# Electrode-Front-End-Analog.net
KiCad netlist of a schematic drawn in Altium Designer
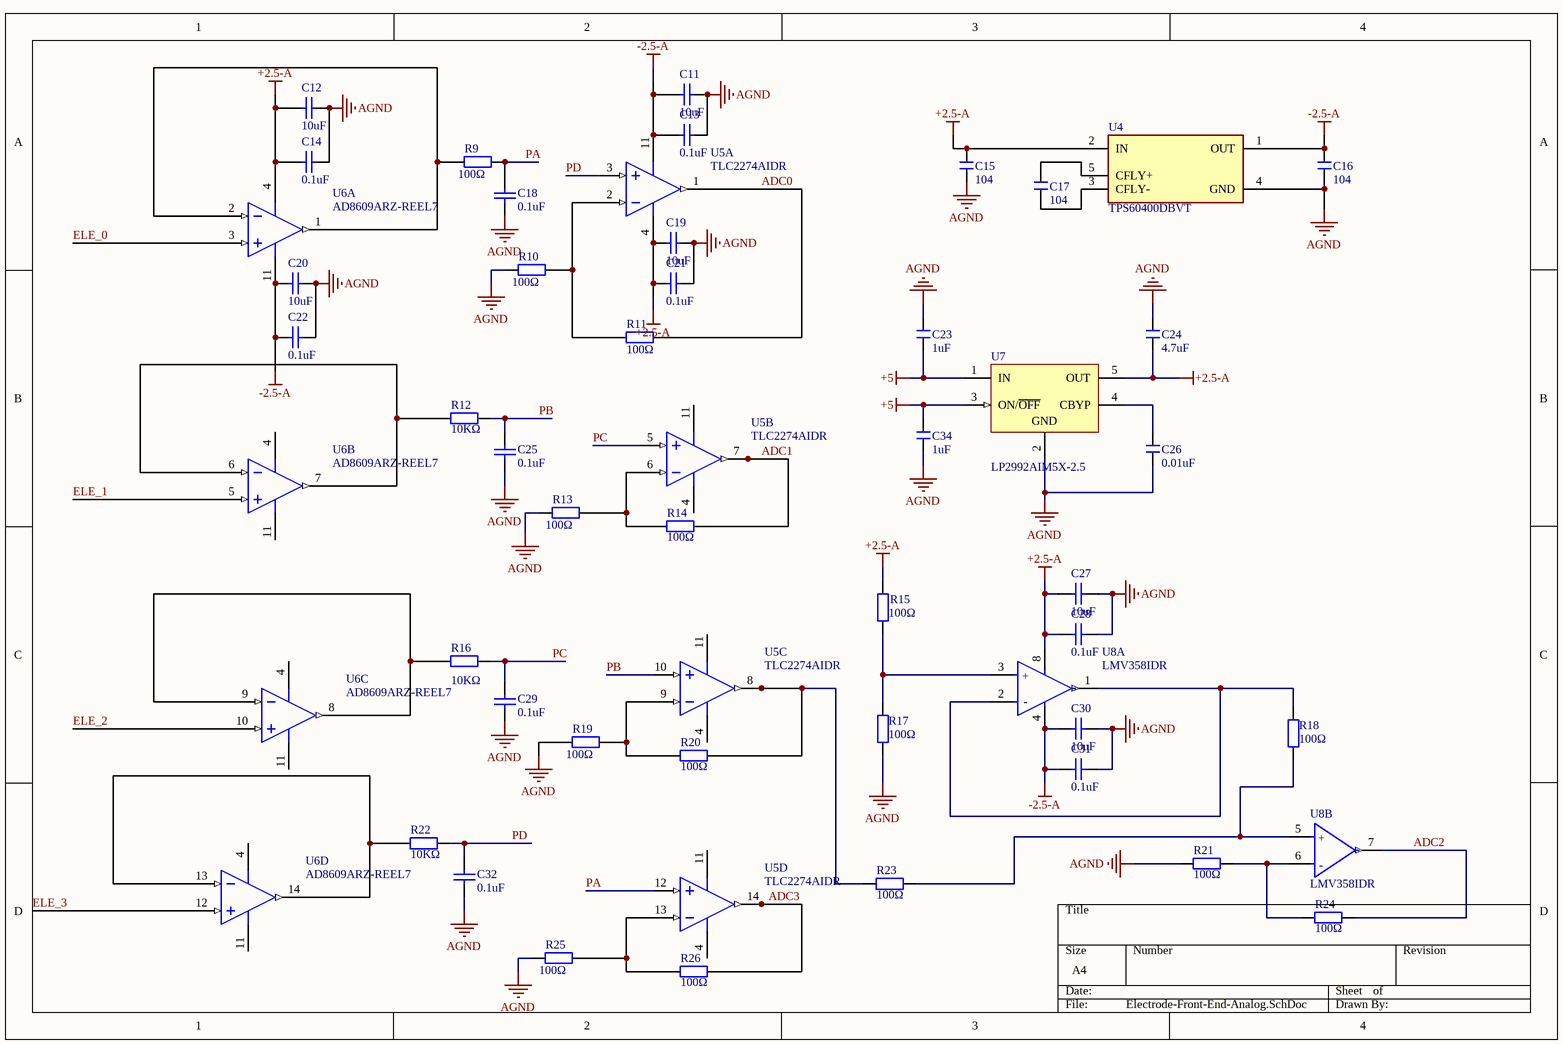
[diagram p0: Electrode-Front-End-Analog.SchDoc]

(export (version "E")
  (design (tool "Eeschema 10.0.6"))
  (components
    (comp (ref "C11")
      (value "10uF")
      (footprint "C 0603_L")
      (description "贴片电容")
      (libsource (lib "Miscellaneous Devices LC") (part "0603 10uF (106) 10% 10V"))
    )
    (comp (ref "C12")
      (value "10uF")
      (footprint "C 0603_L")
      (description "贴片电容")
      (libsource (lib "Miscellaneous Devices LC") (part "0603 10uF (106) 10% 10V"))
    )
    (comp (ref "C13")
      (value "0.1uF")
      (footprint "C 0603_L")
      (description "贴片电容")
      (libsource (lib "Miscellaneous Devices LC") (part "0603 100nF (104) 10% 50V"))
    )
    (comp (ref "C14")
      (value "0.1uF")
      (footprint "C 0603_L")
      (description "贴片电容")
      (libsource (lib "Miscellaneous Devices LC") (part "0603 100nF (104) 10% 50V"))
    )
    (comp (ref "C15")
      (value "104")
      (footprint "C 0603_L")
      (description "无极性贴片电容")
      (libsource (lib "电容-电阻-电感-电位器") (part "C"))
    )
    (comp (ref "C16")
      (value "104")
      (footprint "C 0603_L")
      (description "无极性贴片电容")
      (libsource (lib "电容-电阻-电感-电位器") (part "C"))
    )
    (comp (ref "C17")
      (value "104")
      (footprint "C 0603_L")
      (description "无极性贴片电容")
      (libsource (lib "电容-电阻-电感-电位器") (part "C"))
    )
    (comp (ref "C18")
      (value "0.1uF")
      (footprint "C 0603_L")
      (description "贴片电容")
      (libsource (lib "Miscellaneous Devices LC") (part "0603 100nF (104) 10% 50V"))
    )
    (comp (ref "C19")
      (value "10uF")
      (footprint "C 0603_L")
      (description "贴片电容")
      (libsource (lib "Miscellaneous Devices LC") (part "0603 10uF (106) 10% 10V"))
    )
    (comp (ref "C20")
      (value "10uF")
      (footprint "C 0603_L")
      (description "贴片电容")
      (libsource (lib "Miscellaneous Devices LC") (part "0603 10uF (106) 10% 10V"))
    )
    (comp (ref "C21")
      (value "0.1uF")
      (footprint "C 0603_L")
      (description "贴片电容")
      (libsource (lib "Miscellaneous Devices LC") (part "0603 100nF (104) 10% 50V"))
    )
    (comp (ref "C22")
      (value "0.1uF")
      (footprint "C 0603_L")
      (description "贴片电容")
      (libsource (lib "Miscellaneous Devices LC") (part "0603 100nF (104) 10% 50V"))
    )
    (comp (ref "C23")
      (value "1uF")
      (footprint "C 0603_L")
      (description "无极性贴片电容")
      (libsource (lib "电容-电阻-电感-电位器") (part "C"))
    )
    (comp (ref "C24")
      (value "4.7uF")
      (footprint "C 0603_L")
      (description "无极性贴片电容")
      (libsource (lib "电容-电阻-电感-电位器") (part "C"))
    )
    (comp (ref "C25")
      (value "0.1uF")
      (footprint "C 0603_L")
      (description "贴片电容")
      (libsource (lib "Miscellaneous Devices LC") (part "0603 100nF (104) 10% 50V"))
    )
    (comp (ref "C26")
      (value "0.01uF")
      (footprint "C 0603_L")
      (description "无极性贴片电容")
      (libsource (lib "电容-电阻-电感-电位器") (part "C"))
    )
    (comp (ref "C27")
      (value "10uF")
      (footprint "C 0603_L")
      (description "贴片电容")
      (libsource (lib "Miscellaneous Devices LC") (part "0603 10uF (106) 10% 10V"))
    )
    (comp (ref "C28")
      (value "0.1uF")
      (footprint "C 0603_L")
      (description "贴片电容")
      (libsource (lib "Miscellaneous Devices LC") (part "0603 100nF (104) 10% 50V"))
    )
    (comp (ref "C29")
      (value "0.1uF")
      (footprint "C 0603_L")
      (description "贴片电容")
      (libsource (lib "Miscellaneous Devices LC") (part "0603 100nF (104) 10% 50V"))
    )
    (comp (ref "C30")
      (value "10uF")
      (footprint "C 0603_L")
      (description "贴片电容")
      (libsource (lib "Miscellaneous Devices LC") (part "0603 10uF (106) 10% 10V"))
    )
    (comp (ref "C31")
      (value "0.1uF")
      (footprint "C 0603_L")
      (description "贴片电容")
      (libsource (lib "Miscellaneous Devices LC") (part "0603 100nF (104) 10% 50V"))
    )
    (comp (ref "C32")
      (value "0.1uF")
      (footprint "C 0603_L")
      (description "贴片电容")
      (libsource (lib "Miscellaneous Devices LC") (part "0603 100nF (104) 10% 50V"))
    )
    (comp (ref "C34")
      (value "1uF")
      (footprint "C 0603_L")
      (description "无极性贴片电容")
      (libsource (lib "电容-电阻-电感-电位器") (part "C"))
    )
    (comp (ref "R9")
      (value "100Ω")
      (footprint "R 0603_L")
      (description "贴片电阻")
      (libsource (lib "") (part "0603 100Ω (1000) 1%_1"))
    )
    (comp (ref "R10")
      (value "100Ω")
      (footprint "R 0603_L")
      (description "贴片电阻")
      (libsource (lib "") (part "0603 100Ω (1000) 1%_1"))
    )
    (comp (ref "R11")
      (value "100Ω")
      (footprint "R 0603_L")
      (description "贴片电阻")
      (libsource (lib "") (part "0603 100Ω (1000) 1%_1"))
    )
    (comp (ref "R12")
      (value "10KΩ")
      (footprint "R 0603_L")
      (description "贴片电阻")
      (libsource (lib "") (part "0603 100Ω (1000) 1%_1"))
    )
    (comp (ref "R13")
      (value "100Ω")
      (footprint "R 0603_L")
      (description "贴片电阻")
      (libsource (lib "") (part "0603 100Ω (1000) 1%_1"))
    )
    (comp (ref "R14")
      (value "100Ω")
      (footprint "R 0603_L")
      (description "贴片电阻")
      (libsource (lib "") (part "0603 100Ω (1000) 1%_1"))
    )
    (comp (ref "R15")
      (value "100Ω")
      (footprint "R 0603_L")
      (description "贴片电阻")
      (libsource (lib "") (part "0603 100Ω (1000) 1%_2"))
    )
    (comp (ref "R16")
      (value "10KΩ")
      (footprint "R 0603_L")
      (description "贴片电阻")
      (libsource (lib "") (part "0603 100Ω (1000) 1%_1"))
    )
    (comp (ref "R17")
      (value "100Ω")
      (footprint "R 0603_L")
      (description "贴片电阻")
      (libsource (lib "") (part "0603 100Ω (1000) 1%_2"))
    )
    (comp (ref "R18")
      (value "100Ω")
      (footprint "R 0603_L")
      (description "贴片电阻")
      (libsource (lib "") (part "0603 100Ω (1000) 1%_2"))
    )
    (comp (ref "R19")
      (value "100Ω")
      (footprint "R 0603_L")
      (description "贴片电阻")
      (libsource (lib "") (part "0603 100Ω (1000) 1%_1"))
    )
    (comp (ref "R20")
      (value "100Ω")
      (footprint "R 0603_L")
      (description "贴片电阻")
      (libsource (lib "") (part "0603 100Ω (1000) 1%_1"))
    )
    (comp (ref "R21")
      (value "100Ω")
      (footprint "R 0603_L")
      (description "贴片电阻")
      (libsource (lib "Miscellaneous Devices LC") (part "0603 100Ω (1000) 1%"))
    )
    (comp (ref "R22")
      (value "10KΩ")
      (footprint "R 0603_L")
      (description "贴片电阻")
      (libsource (lib "") (part "0603 100Ω (1000) 1%_1"))
    )
    (comp (ref "R23")
      (value "100Ω")
      (footprint "R 0603_L")
      (description "贴片电阻")
      (libsource (lib "Miscellaneous Devices LC") (part "0603 100Ω (1000) 1%"))
    )
    (comp (ref "R24")
      (value "100Ω")
      (footprint "R 0603_L")
      (description "贴片电阻")
      (libsource (lib "Miscellaneous Devices LC") (part "0603 100Ω (1000) 1%"))
    )
    (comp (ref "R25")
      (value "100Ω")
      (footprint "R 0603_L")
      (description "贴片电阻")
      (libsource (lib "") (part "0603 100Ω (1000) 1%_1"))
    )
    (comp (ref "R26")
      (value "100Ω")
      (footprint "R 0603_L")
      (description "贴片电阻")
      (libsource (lib "") (part "0603 100Ω (1000) 1%_1"))
    )
    (comp (ref "U4")
      (value "TPS60400DBVT")
      (footprint "FP-DBV0005A-IPC_C")
      (description "IC REG CHARG PUMP INV 60MA SOT23")
      (libsource (lib "Altium Content Vault") (part "419acff30fa379e0ae0717d32e86a44"))
    )
    (comp (ref "U5")
      (value "TLC2274AIDR")
      (footprint "D0014A_L")
      (fields (field (name "MANUFACTURER") "Texas Instruments"))
      (libsource (lib "Altium Content Vault") (part "TI-TLC2274X-14"))
    )
    (comp (ref "U6")
      (value "AD8609ARZ-REEL7")
      (footprint "ADI-R-14_N")
      (fields (field (name "MANUFACTURER") "Analog Devices") (field (name "GENERIC PART NUMBER") "AD8609"))
      (libsource (lib "Altium Content Vault") (part "ADI-ADxxxx_OPxxxx-X-14"))
    )
    (comp (ref "U7")
      (value "LP2992AIM5X-2.5")
      (footprint "MF05A_M")
      (description "Micropower 250 mA Low-Noise Ultra Low-Dropout Regulator, 5-pin SOT-23")
      (fields (field (name "MANUFACTURER") "National Semiconductor"))
      (libsource (lib "Altium Content Vault") (part "PM-REG-LP2985-SOT5"))
    )
    (comp (ref "U8")
      (value "LMV358IDR")
      (footprint "FP-D0008A-MFG")
      (description "IC OPAMP GP 2 CIRCUIT 8SOIC")
      (libsource (lib "Altium Content Vault") (part "1f85fec4e6914445158f776dbf16c1d"))
    )
  )
  (nets
    (net (code "1") (name "+2.5-A") (class "Default")
      (node (ref "C12") (pin "1") (pinfunction "1_1") (pintype "passive"))
      (node (ref "C14") (pin "1") (pinfunction "1_1") (pintype "passive"))
      (node (ref "C15") (pin "2") (pinfunction "2_2") (pintype "passive"))
      (node (ref "C19") (pin "1") (pinfunction "1_1") (pintype "passive"))
      (node (ref "C21") (pin "1") (pinfunction "1_1") (pintype "passive"))
      (node (ref "C24") (pin "1") (pinfunction "1_1") (pintype "passive"))
      (node (ref "C27") (pin "1") (pinfunction "1_1") (pintype "passive"))
      (node (ref "C28") (pin "1") (pinfunction "1_1") (pintype "passive"))
      (node (ref "R15") (pin "2") (pinfunction "2_2") (pintype "passive"))
      (node (ref "U4") (pin "2") (pinfunction "IN_2") (pintype "power_in"))
      (node (ref "U5") (pin "4") (pinfunction "VDD+_4") (pintype "power_in"))
      (node (ref "U6") (pin "4") (pinfunction "+V_4") (pintype "power_in"))
      (node (ref "U7") (pin "5") (pinfunction "OUT_5") (pintype "power_in"))
      (node (ref "U8") (pin "8") (pinfunction "VCC+_8") (pintype "power_in"))
    )
    (net (code "2") (name "+5") (class "Default")
      (node (ref "C23") (pin "1") (pinfunction "1_1") (pintype "passive"))
      (node (ref "C34") (pin "1") (pinfunction "1_1") (pintype "passive"))
      (node (ref "U7") (pin "1") (pinfunction "IN_1") (pintype "power_in"))
      (node (ref "U7") (pin "3") (pinfunction "ON/~{OFF}_3") (pintype "input"))
    )
    (net (code "3") (name "-2.5-A") (class "Default")
      (node (ref "C11") (pin "1") (pinfunction "1_1") (pintype "passive"))
      (node (ref "C13") (pin "1") (pinfunction "1_1") (pintype "passive"))
      (node (ref "C16") (pin "2") (pinfunction "2_2") (pintype "passive"))
      (node (ref "C20") (pin "1") (pinfunction "1_1") (pintype "passive"))
      (node (ref "C22") (pin "1") (pinfunction "1_1") (pintype "passive"))
      (node (ref "C30") (pin "1") (pinfunction "1_1") (pintype "passive"))
      (node (ref "C31") (pin "1") (pinfunction "1_1") (pintype "passive"))
      (node (ref "U4") (pin "1") (pinfunction "OUT_1") (pintype "power_in"))
      (node (ref "U5") (pin "11") (pinfunction "VDD-_11") (pintype "power_in"))
      (node (ref "U6") (pin "11") (pinfunction "-V_11") (pintype "power_in"))
      (node (ref "U8") (pin "4") (pinfunction "GND_4") (pintype "power_in"))
    )
    (net (code "4") (name "/ADC0") (class "Default")
      (node (ref "R11") (pin "2") (pinfunction "2_2") (pintype "passive"))
      (node (ref "U5") (pin "1") (pinfunction "OUT1_1") (pintype "output"))
    )
    (net (code "5") (name "/ADC1") (class "Default")
      (node (ref "R14") (pin "2") (pinfunction "2_2") (pintype "passive"))
      (node (ref "U5") (pin "7") (pinfunction "OUT2_7") (pintype "output"))
    )
    (net (code "6") (name "/ADC2") (class "Default")
      (node (ref "R24") (pin "1") (pinfunction "1_1") (pintype "passive"))
      (node (ref "U8") (pin "7") (pinfunction "2OUT_7") (pintype "output"))
    )
    (net (code "7") (name "/ADC3") (class "Default")
      (node (ref "R26") (pin "2") (pinfunction "2_2") (pintype "passive"))
      (node (ref "U5") (pin "14") (pinfunction "OUT4_14") (pintype "output"))
    )
    (net (code "8") (name "/ELE_0") (class "Default")
      (node (ref "U6") (pin "3") (pinfunction "+IN_A_3") (pintype "input"))
    )
    (net (code "9") (name "/ELE_1") (class "Default")
      (node (ref "U6") (pin "5") (pinfunction "+IN_B_5") (pintype "input"))
    )
    (net (code "10") (name "/ELE_2") (class "Default")
      (node (ref "U6") (pin "10") (pinfunction "+IN_C_10") (pintype "input"))
    )
    (net (code "11") (name "/ELE_3") (class "Default")
      (node (ref "U6") (pin "12") (pinfunction "+IN_D_12") (pintype "input"))
    )
    (net (code "12") (name "/PA") (class "Default")
      (node (ref "C18") (pin "2") (pinfunction "2_2") (pintype "passive"))
      (node (ref "R9") (pin "2") (pinfunction "2_2") (pintype "passive"))
      (node (ref "U5") (pin "12") (pinfunction "IN4+_12") (pintype "input"))
    )
    (net (code "13") (name "/PB") (class "Default")
      (node (ref "C25") (pin "2") (pinfunction "2_2") (pintype "passive"))
      (node (ref "R12") (pin "2") (pinfunction "2_2") (pintype "passive"))
      (node (ref "U5") (pin "10") (pinfunction "IN3+_10") (pintype "input"))
    )
    (net (code "14") (name "/PC") (class "Default")
      (node (ref "C29") (pin "2") (pinfunction "2_2") (pintype "passive"))
      (node (ref "R16") (pin "2") (pinfunction "2_2") (pintype "passive"))
      (node (ref "U5") (pin "5") (pinfunction "IN2+_5") (pintype "input"))
    )
    (net (code "15") (name "/PD") (class "Default")
      (node (ref "C32") (pin "2") (pinfunction "2_2") (pintype "passive"))
      (node (ref "R22") (pin "2") (pinfunction "2_2") (pintype "passive"))
      (node (ref "U5") (pin "3") (pinfunction "IN1+_3") (pintype "input"))
    )
    (net (code "16") (name "AGND") (class "Default")
      (node (ref "C11") (pin "2") (pinfunction "2_2") (pintype "passive"))
      (node (ref "C12") (pin "2") (pinfunction "2_2") (pintype "passive"))
      (node (ref "C13") (pin "2") (pinfunction "2_2") (pintype "passive"))
      (node (ref "C14") (pin "2") (pinfunction "2_2") (pintype "passive"))
      (node (ref "C15") (pin "1") (pinfunction "1_1") (pintype "passive"))
      (node (ref "C16") (pin "1") (pinfunction "1_1") (pintype "passive"))
      (node (ref "C18") (pin "1") (pinfunction "1_1") (pintype "passive"))
      (node (ref "C19") (pin "2") (pinfunction "2_2") (pintype "passive"))
      (node (ref "C20") (pin "2") (pinfunction "2_2") (pintype "passive"))
      (node (ref "C21") (pin "2") (pinfunction "2_2") (pintype "passive"))
      (node (ref "C22") (pin "2") (pinfunction "2_2") (pintype "passive"))
      (node (ref "C23") (pin "2") (pinfunction "2_2") (pintype "passive"))
      (node (ref "C24") (pin "2") (pinfunction "2_2") (pintype "passive"))
      (node (ref "C25") (pin "1") (pinfunction "1_1") (pintype "passive"))
      (node (ref "C26") (pin "2") (pinfunction "2_2") (pintype "passive"))
      (node (ref "C27") (pin "2") (pinfunction "2_2") (pintype "passive"))
      (node (ref "C28") (pin "2") (pinfunction "2_2") (pintype "passive"))
      (node (ref "C29") (pin "1") (pinfunction "1_1") (pintype "passive"))
      (node (ref "C30") (pin "2") (pinfunction "2_2") (pintype "passive"))
      (node (ref "C31") (pin "2") (pinfunction "2_2") (pintype "passive"))
      (node (ref "C32") (pin "1") (pinfunction "1_1") (pintype "passive"))
      (node (ref "C34") (pin "2") (pinfunction "2_2") (pintype "passive"))
      (node (ref "R10") (pin "1") (pinfunction "1_1") (pintype "passive"))
      (node (ref "R13") (pin "1") (pinfunction "1_1") (pintype "passive"))
      (node (ref "R17") (pin "1") (pinfunction "1_1") (pintype "passive"))
      (node (ref "R19") (pin "1") (pinfunction "1_1") (pintype "passive"))
      (node (ref "R21") (pin "2") (pinfunction "2_2") (pintype "passive"))
      (node (ref "R25") (pin "1") (pinfunction "1_1") (pintype "passive"))
      (node (ref "U4") (pin "4") (pinfunction "GND_4") (pintype "power_in"))
      (node (ref "U7") (pin "2") (pinfunction "GND_2") (pintype "power_in"))
    )
    (net (code "17") (name "Net-(U4-CFLY+)") (class "Default")
      (node (ref "C17") (pin "2") (pinfunction "2_2") (pintype "passive"))
      (node (ref "U4") (pin "5") (pinfunction "CFLY+_5") (pintype "passive"))
    )
    (net (code "18") (name "Net-(U4-CFLY-)") (class "Default")
      (node (ref "C17") (pin "1") (pinfunction "1_1") (pintype "passive"))
      (node (ref "U4") (pin "3") (pinfunction "CFLY-_3") (pintype "passive"))
    )
    (net (code "19") (name "Net-(U5A-IN1-)") (class "Default")
      (node (ref "R10") (pin "2") (pinfunction "2_2") (pintype "passive"))
      (node (ref "R11") (pin "1") (pinfunction "1_1") (pintype "passive"))
      (node (ref "U5") (pin "2") (pinfunction "IN1-_2") (pintype "input"))
    )
    (net (code "20") (name "Net-(U5B-IN2-)") (class "Default")
      (node (ref "R13") (pin "2") (pinfunction "2_2") (pintype "passive"))
      (node (ref "R14") (pin "1") (pinfunction "1_1") (pintype "passive"))
      (node (ref "U5") (pin "6") (pinfunction "IN2-_6") (pintype "input"))
    )
    (net (code "21") (name "Net-(U5C-IN3-)") (class "Default")
      (node (ref "R19") (pin "2") (pinfunction "2_2") (pintype "passive"))
      (node (ref "R20") (pin "1") (pinfunction "1_1") (pintype "passive"))
      (node (ref "U5") (pin "9") (pinfunction "IN3-_9") (pintype "input"))
    )
    (net (code "22") (name "Net-(U5C-OUT3)") (class "Default")
      (node (ref "R20") (pin "2") (pinfunction "2_2") (pintype "passive"))
      (node (ref "R23") (pin "2") (pinfunction "2_2") (pintype "passive"))
      (node (ref "U5") (pin "8") (pinfunction "OUT3_8") (pintype "output"))
    )
    (net (code "23") (name "Net-(U5D-IN4-)") (class "Default")
      (node (ref "R25") (pin "2") (pinfunction "2_2") (pintype "passive"))
      (node (ref "R26") (pin "1") (pinfunction "1_1") (pintype "passive"))
      (node (ref "U5") (pin "13") (pinfunction "IN4-_13") (pintype "input"))
    )
    (net (code "24") (name "Net-(U6A--IN_A)") (class "Default")
      (node (ref "R9") (pin "1") (pinfunction "1_1") (pintype "passive"))
      (node (ref "U6") (pin "1") (pinfunction "OUT_A_1") (pintype "output"))
      (node (ref "U6") (pin "2") (pinfunction "-IN_A_2") (pintype "input"))
    )
    (net (code "25") (name "Net-(U6B--IN_B)") (class "Default")
      (node (ref "R12") (pin "1") (pinfunction "1_1") (pintype "passive"))
      (node (ref "U6") (pin "6") (pinfunction "-IN_B_6") (pintype "input"))
      (node (ref "U6") (pin "7") (pinfunction "OUT_B_7") (pintype "output"))
    )
    (net (code "26") (name "Net-(U6C--IN_C)") (class "Default")
      (node (ref "R16") (pin "1") (pinfunction "1_1") (pintype "passive"))
      (node (ref "U6") (pin "8") (pinfunction "OUT_C_8") (pintype "output"))
      (node (ref "U6") (pin "9") (pinfunction "-IN_C_9") (pintype "input"))
    )
    (net (code "27") (name "Net-(U6D--IN_D)") (class "Default")
      (node (ref "R22") (pin "1") (pinfunction "1_1") (pintype "passive"))
      (node (ref "U6") (pin "13") (pinfunction "-IN_D_13") (pintype "input"))
      (node (ref "U6") (pin "14") (pinfunction "OUT_D_14") (pintype "output"))
    )
    (net (code "28") (name "Net-(U7-CBYP)") (class "Default")
      (node (ref "C26") (pin "1") (pinfunction "1_1") (pintype "passive"))
      (node (ref "U7") (pin "4") (pinfunction "CBYP_4") (pintype "passive"))
    )
    (net (code "29") (name "Net-(U8A-1IN+)") (class "Default")
      (node (ref "R15") (pin "1") (pinfunction "1_1") (pintype "passive"))
      (node (ref "R17") (pin "2") (pinfunction "2_2") (pintype "passive"))
      (node (ref "U8") (pin "3") (pinfunction "1IN+_3") (pintype "tri_state"))
    )
    (net (code "30") (name "Net-(U8A-1IN-)") (class "Default")
      (node (ref "R18") (pin "2") (pinfunction "2_2") (pintype "passive"))
      (node (ref "U8") (pin "1") (pinfunction "OUT_1") (pintype "output"))
      (node (ref "U8") (pin "2") (pinfunction "1IN-_2") (pintype "tri_state"))
    )
    (net (code "31") (name "Net-(U8B-2IN+)") (class "Default")
      (node (ref "R18") (pin "1") (pinfunction "1_1") (pintype "passive"))
      (node (ref "R23") (pin "1") (pinfunction "1_1") (pintype "passive"))
      (node (ref "U8") (pin "5") (pinfunction "2IN+_5") (pintype "tri_state"))
    )
    (net (code "32") (name "Net-(U8B-2IN-)") (class "Default")
      (node (ref "R21") (pin "1") (pinfunction "1_1") (pintype "passive"))
      (node (ref "R24") (pin "2") (pinfunction "2_2") (pintype "passive"))
      (node (ref "U8") (pin "6") (pinfunction "2IN-_6") (pintype "tri_state"))
    )
    (net (code "33") (name "unconnected-(U5B-VDD+-Pad4)") (class "Default")
      (node (ref "U5") (pin "4") (pinfunction "VDD+_4") (pintype "power_in"))
    )
    (net (code "34") (name "unconnected-(U5B-VDD--Pad11)") (class "Default")
      (node (ref "U5") (pin "11") (pinfunction "VDD-_11") (pintype "power_in"))
    )
    (net (code "35") (name "unconnected-(U5C-VDD+-Pad4)") (class "Default")
      (node (ref "U5") (pin "4") (pinfunction "VDD+_4") (pintype "power_in"))
    )
    (net (code "36") (name "unconnected-(U5C-VDD--Pad11)") (class "Default")
      (node (ref "U5") (pin "11") (pinfunction "VDD-_11") (pintype "power_in"))
    )
    (net (code "37") (name "unconnected-(U5D-VDD+-Pad4)") (class "Default")
      (node (ref "U5") (pin "4") (pinfunction "VDD+_4") (pintype "power_in"))
    )
    (net (code "38") (name "unconnected-(U5D-VDD--Pad11)") (class "Default")
      (node (ref "U5") (pin "11") (pinfunction "VDD-_11") (pintype "power_in"))
    )
    (net (code "39") (name "unconnected-(U6B-+V-Pad4)") (class "Default")
      (node (ref "U6") (pin "4") (pinfunction "+V_4") (pintype "power_in"))
    )
    (net (code "40") (name "unconnected-(U6B--V-Pad11)") (class "Default")
      (node (ref "U6") (pin "11") (pinfunction "-V_11") (pintype "power_in"))
    )
    (net (code "41") (name "unconnected-(U6C-+V-Pad4)") (class "Default")
      (node (ref "U6") (pin "4") (pinfunction "+V_4") (pintype "power_in"))
    )
    (net (code "42") (name "unconnected-(U6C--V-Pad11)") (class "Default")
      (node (ref "U6") (pin "11") (pinfunction "-V_11") (pintype "power_in"))
    )
    (net (code "43") (name "unconnected-(U6D-+V-Pad4)") (class "Default")
      (node (ref "U6") (pin "4") (pinfunction "+V_4") (pintype "power_in"))
    )
    (net (code "44") (name "unconnected-(U6D--V-Pad11)") (class "Default")
      (node (ref "U6") (pin "11") (pinfunction "-V_11") (pintype "power_in"))
    )
  )
)
